# 3_PWR.net
KiCad netlist of a schematic drawn in Altium Designer
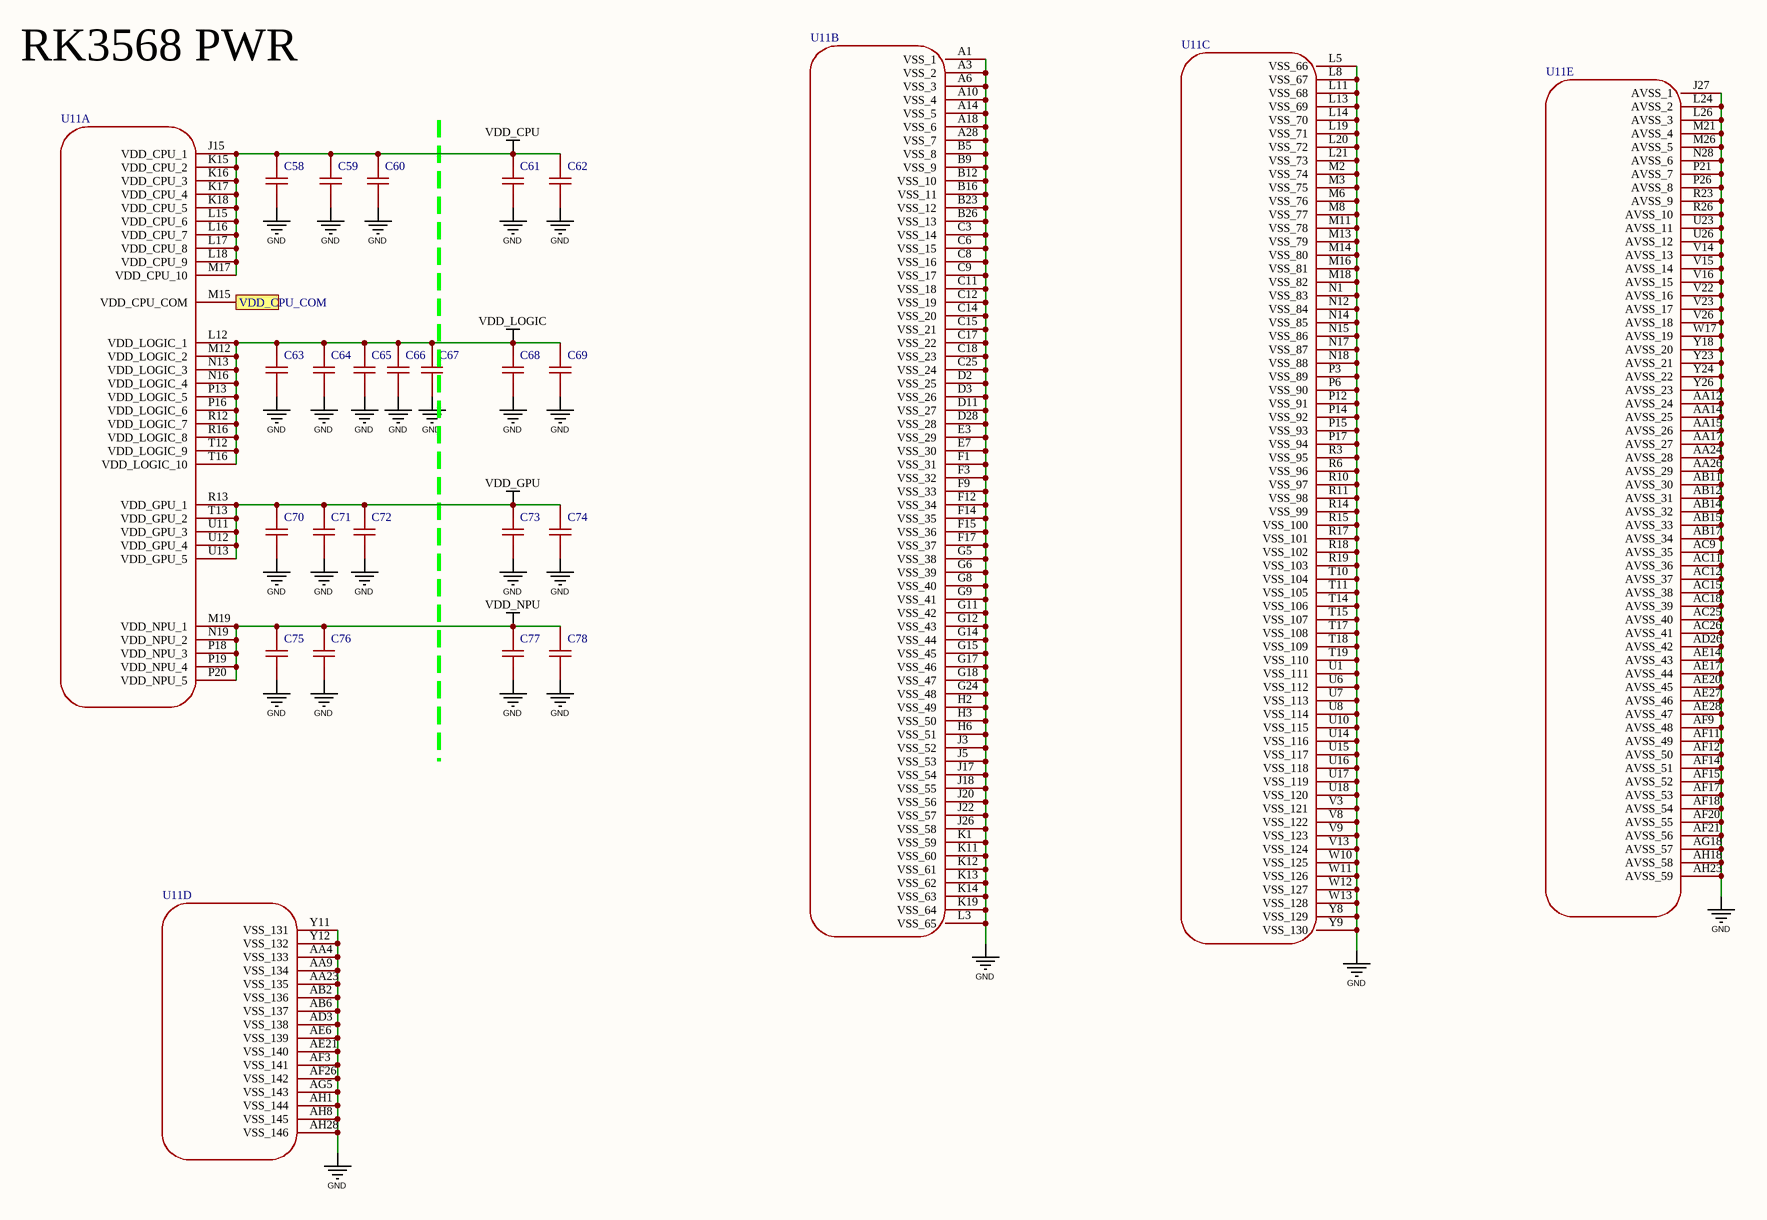
[diagram p0: 3_PWR.schdoc]

(export (version "E")
  (design (tool "Eeschema 10.0.6"))
  (components
    (comp (ref "C58")
      (value "100nF")
      (footprint "C0201")
      (description "容值:100nF;精度:±10%;额定电压:16V;材质(温度系数):X5R;")
      (fields
        (field (name "MANUFACTURER") "SAMSUNG(三星)")
        (field (name "MANUFACTURER PART") "CL03A104KO3NNNC")
      )
      (libsource (lib "altium-import") (part "root_0_CL03A104KO3NNNC_"))
    )
    (comp (ref "C59")
      (value "1uF")
      (footprint "C0402")
      (description "容值:1uF;精度:±10%;额定电压:25V;材质(温度系数):X5R;")
      (fields
        (field (name "MANUFACTURER") "SAMSUNG(三星)")
        (field (name "MANUFACTURER PART") "CL05A105KA5NQNC")
      )
      (libsource (lib "altium-import") (part "root_1_CL05A105KA5NQNC_"))
    )
    (comp (ref "C60")
      (value "22uF")
      (footprint "C0603")
      (description "容值:22uF;精度:±20%;额定电压:10V;材质(温度系数):X5R;")
      (fields
        (field (name "MANUFACTURER") "SAMSUNG(三星)")
        (field (name "MANUFACTURER PART") "CL10A226MP8NUNE")
      )
      (libsource (lib "altium-import") (part "root_1_CL10A226MP8NUNE_"))
    )
    (comp (ref "C61")
      (value "22uF")
      (footprint "C0603")
      (description "容值:22uF;精度:±20%;额定电压:10V;材质(温度系数):X5R;")
      (fields
        (field (name "MANUFACTURER") "SAMSUNG(三星)")
        (field (name "MANUFACTURER PART") "CL10A226MP8NUNE")
      )
      (libsource (lib "altium-import") (part "root_1_CL10A226MP8NUNE_"))
    )
    (comp (ref "C62")
      (value "22uF")
      (footprint "C0603")
      (description "容值:22uF;精度:±20%;额定电压:10V;材质(温度系数):X5R;")
      (fields
        (field (name "MANUFACTURER") "SAMSUNG(三星)")
        (field (name "MANUFACTURER PART") "CL10A226MP8NUNE")
      )
      (libsource (lib "altium-import") (part "root_1_CL10A226MP8NUNE_"))
    )
    (comp (ref "C63")
      (value "100nF")
      (footprint "C0201")
      (description "容值:100nF;精度:±10%;额定电压:16V;材质(温度系数):X5R;")
      (fields
        (field (name "MANUFACTURER") "SAMSUNG(三星)")
        (field (name "MANUFACTURER PART") "CL03A104KO3NNNC")
      )
      (libsource (lib "altium-import") (part "root_0_CL03A104KO3NNNC_"))
    )
    (comp (ref "C64")
      (value "4.7uF")
      (footprint "C0201")
      (description "容值:4.7uF;精度:±20%;额定电压:6.3V;材质(温度系数):X5R;")
      (fields
        (field (name "MANUFACTURER") "muRata(村田)")
        (field (name "MANUFACTURER PART") "GRM035R60J475ME15D")
      )
      (libsource (lib "altium-import") (part "root_0_GRM035R60J475ME15D_"))
    )
    (comp (ref "C65")
      (value "1uF")
      (footprint "C0402")
      (description "容值:1uF;精度:±10%;额定电压:25V;材质(温度系数):X5R;")
      (fields
        (field (name "MANUFACTURER") "SAMSUNG(三星)")
        (field (name "MANUFACTURER PART") "CL05A105KA5NQNC")
      )
      (libsource (lib "altium-import") (part "root_1_CL05A105KA5NQNC_"))
    )
    (comp (ref "C66")
      (value "1uF")
      (footprint "C0402")
      (description "容值:1uF;精度:±10%;额定电压:25V;材质(温度系数):X5R;")
      (fields
        (field (name "MANUFACTURER") "SAMSUNG(三星)")
        (field (name "MANUFACTURER PART") "CL05A105KA5NQNC")
      )
      (libsource (lib "altium-import") (part "root_1_CL05A105KA5NQNC_"))
    )
    (comp (ref "C67")
      (value "22uF")
      (footprint "C0603")
      (description "容值:22uF;精度:±20%;额定电压:10V;材质(温度系数):X5R;")
      (fields
        (field (name "MANUFACTURER") "SAMSUNG(三星)")
        (field (name "MANUFACTURER PART") "CL10A226MP8NUNE")
      )
      (libsource (lib "altium-import") (part "root_1_CL10A226MP8NUNE_"))
    )
    (comp (ref "C68")
      (value "22uF")
      (footprint "C0603")
      (description "容值:22uF;精度:±20%;额定电压:10V;材质(温度系数):X5R;")
      (fields
        (field (name "MANUFACTURER") "SAMSUNG(三星)")
        (field (name "MANUFACTURER PART") "CL10A226MP8NUNE")
      )
      (libsource (lib "altium-import") (part "root_1_CL10A226MP8NUNE_"))
    )
    (comp (ref "C69")
      (value "10uF")
      (footprint "C0402")
      (description "容值:10uF;精度:±20%;额定电压:10V;材质(温度系数):X5R;")
      (fields
        (field (name "MANUFACTURER") "SAMSUNG(三星)")
        (field (name "MANUFACTURER PART") "CL05A106MP5NUNC")
      )
      (libsource (lib "altium-import") (part "root_1_CL05A106MP5NUNC_"))
    )
    (comp (ref "C70")
      (value "100nF")
      (footprint "C0201")
      (description "容值:100nF;精度:±10%;额定电压:16V;材质(温度系数):X5R;")
      (fields
        (field (name "MANUFACTURER") "SAMSUNG(三星)")
        (field (name "MANUFACTURER PART") "CL03A104KO3NNNC")
      )
      (libsource (lib "altium-import") (part "root_0_CL03A104KO3NNNC_"))
    )
    (comp (ref "C71")
      (value "4.7uF")
      (footprint "C0201")
      (description "容值:4.7uF;精度:±20%;额定电压:6.3V;材质(温度系数):X5R;")
      (fields
        (field (name "MANUFACTURER") "muRata(村田)")
        (field (name "MANUFACTURER PART") "GRM035R60J475ME15D")
      )
      (libsource (lib "altium-import") (part "root_0_GRM035R60J475ME15D_"))
    )
    (comp (ref "C72")
      (value "22uF")
      (footprint "C0603")
      (description "容值:22uF;精度:±20%;额定电压:10V;材质(温度系数):X5R;")
      (fields
        (field (name "MANUFACTURER") "SAMSUNG(三星)")
        (field (name "MANUFACTURER PART") "CL10A226MP8NUNE")
      )
      (libsource (lib "altium-import") (part "root_1_CL10A226MP8NUNE_"))
    )
    (comp (ref "C73")
      (value "22uF")
      (footprint "C0603")
      (description "容值:22uF;精度:±20%;额定电压:10V;材质(温度系数):X5R;")
      (fields
        (field (name "MANUFACTURER") "SAMSUNG(三星)")
        (field (name "MANUFACTURER PART") "CL10A226MP8NUNE")
      )
      (libsource (lib "altium-import") (part "root_1_CL10A226MP8NUNE_"))
    )
    (comp (ref "C74")
      (value "10uF")
      (footprint "C0402")
      (description "容值:10uF;精度:±20%;额定电压:10V;材质(温度系数):X5R;")
      (fields
        (field (name "MANUFACTURER") "SAMSUNG(三星)")
        (field (name "MANUFACTURER PART") "CL05A106MP5NUNC")
      )
      (libsource (lib "altium-import") (part "root_1_CL05A106MP5NUNC_"))
    )
    (comp (ref "C75")
      (value "100nF")
      (footprint "C0201")
      (description "容值:100nF;精度:±10%;额定电压:16V;材质(温度系数):X5R;")
      (fields
        (field (name "MANUFACTURER") "SAMSUNG(三星)")
        (field (name "MANUFACTURER PART") "CL03A104KO3NNNC")
      )
      (libsource (lib "altium-import") (part "root_0_CL03A104KO3NNNC_"))
    )
    (comp (ref "C76")
      (value "22uF")
      (footprint "C0603")
      (description "容值:22uF;精度:±20%;额定电压:10V;材质(温度系数):X5R;")
      (fields
        (field (name "MANUFACTURER") "SAMSUNG(三星)")
        (field (name "MANUFACTURER PART") "CL10A226MP8NUNE")
      )
      (libsource (lib "altium-import") (part "root_1_CL10A226MP8NUNE_"))
    )
    (comp (ref "C77")
      (value "22uF")
      (footprint "C0603")
      (description "容值:22uF;精度:±20%;额定电压:10V;材质(温度系数):X5R;")
      (fields
        (field (name "MANUFACTURER") "SAMSUNG(三星)")
        (field (name "MANUFACTURER PART") "CL10A226MP8NUNE")
      )
      (libsource (lib "altium-import") (part "root_1_CL10A226MP8NUNE_"))
    )
    (comp (ref "C78")
      (value "10uF")
      (footprint "C0402")
      (description "容值:10uF;精度:±20%;额定电压:10V;材质(温度系数):X5R;")
      (fields
        (field (name "MANUFACTURER") "SAMSUNG(三星)")
        (field (name "MANUFACTURER PART") "CL05A106MP5NUNC")
      )
      (libsource (lib "altium-import") (part "root_1_CL05A106MP5NUNC_"))
    )
    (comp (ref "U11")
      (value "SOC_RK3568")
      (footprint "RK3568")
      (fields (field (name "MANUFACTURER") "Rockchip (瑞芯微)") (field (name "CREATED BY") "JJJ"))
      (libsource (lib "altium-import") (part "root_0_SOC_RK3568_"))
    )
  )
  (nets
    (net (code "1") (name "/VDD_CPU_COM") (class "Default")
      (node (ref "U11") (pin "M15") (pinfunction "VDD_CPU_COM_M15") (pintype "passive"))
    )
    (net (code "2") (name "GND") (class "Default")
      (node (ref "C58") (pin "1") (pinfunction "1_1") (pintype "passive"))
      (node (ref "C59") (pin "1") (pinfunction "1_1") (pintype "passive"))
      (node (ref "C60") (pin "1") (pinfunction "1_1") (pintype "passive"))
      (node (ref "C61") (pin "1") (pinfunction "1_1") (pintype "passive"))
      (node (ref "C62") (pin "1") (pinfunction "1_1") (pintype "passive"))
      (node (ref "C63") (pin "1") (pinfunction "1_1") (pintype "passive"))
      (node (ref "C64") (pin "1") (pinfunction "1_1") (pintype "passive"))
      (node (ref "C65") (pin "1") (pinfunction "1_1") (pintype "passive"))
      (node (ref "C66") (pin "1") (pinfunction "1_1") (pintype "passive"))
      (node (ref "C67") (pin "1") (pinfunction "1_1") (pintype "passive"))
      (node (ref "C68") (pin "1") (pinfunction "1_1") (pintype "passive"))
      (node (ref "C69") (pin "1") (pinfunction "1_1") (pintype "passive"))
      (node (ref "C70") (pin "1") (pinfunction "1_1") (pintype "passive"))
      (node (ref "C71") (pin "1") (pinfunction "1_1") (pintype "passive"))
      (node (ref "C72") (pin "1") (pinfunction "1_1") (pintype "passive"))
      (node (ref "C73") (pin "1") (pinfunction "1_1") (pintype "passive"))
      (node (ref "C74") (pin "1") (pinfunction "1_1") (pintype "passive"))
      (node (ref "C75") (pin "1") (pinfunction "1_1") (pintype "passive"))
      (node (ref "C76") (pin "1") (pinfunction "1_1") (pintype "passive"))
      (node (ref "C77") (pin "1") (pinfunction "1_1") (pintype "passive"))
      (node (ref "C78") (pin "1") (pinfunction "1_1") (pintype "passive"))
      (node (ref "U11") (pin "A1") (pinfunction "VSS_1_A1") (pintype "passive"))
      (node (ref "U11") (pin "A10") (pinfunction "VSS_4_A10") (pintype "passive"))
      (node (ref "U11") (pin "A14") (pinfunction "VSS_5_A14") (pintype "passive"))
      (node (ref "U11") (pin "A18") (pinfunction "VSS_6_A18") (pintype "passive"))
      (node (ref "U11") (pin "A28") (pinfunction "VSS_7_A28") (pintype "passive"))
      (node (ref "U11") (pin "A3") (pinfunction "VSS_2_A3") (pintype "passive"))
      (node (ref "U11") (pin "A6") (pinfunction "VSS_3_A6") (pintype "passive"))
      (node (ref "U11") (pin "AA12") (pinfunction "AVSS_24_AA12") (pintype "passive"))
      (node (ref "U11") (pin "AA14") (pinfunction "AVSS_25_AA14") (pintype "passive"))
      (node (ref "U11") (pin "AA15") (pinfunction "AVSS_26_AA15") (pintype "passive"))
      (node (ref "U11") (pin "AA17") (pinfunction "AVSS_27_AA17") (pintype "passive"))
      (node (ref "U11") (pin "AA23") (pinfunction "VSS_135_AA23") (pintype "passive"))
      (node (ref "U11") (pin "AA24") (pinfunction "AVSS_28_AA24") (pintype "passive"))
      (node (ref "U11") (pin "AA26") (pinfunction "AVSS_29_AA26") (pintype "passive"))
      (node (ref "U11") (pin "AA4") (pinfunction "VSS_133_AA4") (pintype "passive"))
      (node (ref "U11") (pin "AA9") (pinfunction "VSS_134_AA9") (pintype "passive"))
      (node (ref "U11") (pin "AB11") (pinfunction "AVSS_30_AB11") (pintype "passive"))
      (node (ref "U11") (pin "AB12") (pinfunction "AVSS_31_AB12") (pintype "passive"))
      (node (ref "U11") (pin "AB14") (pinfunction "AVSS_32_AB14") (pintype "passive"))
      (node (ref "U11") (pin "AB15") (pinfunction "AVSS_33_AB15") (pintype "passive"))
      (node (ref "U11") (pin "AB17") (pinfunction "AVSS_34_AB17") (pintype "passive"))
      (node (ref "U11") (pin "AB2") (pinfunction "VSS_136_AB2") (pintype "passive"))
      (node (ref "U11") (pin "AB6") (pinfunction "VSS_137_AB6") (pintype "passive"))
      (node (ref "U11") (pin "AC11") (pinfunction "AVSS_36_AC11") (pintype "passive"))
      (node (ref "U11") (pin "AC12") (pinfunction "AVSS_37_AC12") (pintype "passive"))
      (node (ref "U11") (pin "AC15") (pinfunction "AVSS_38_AC15") (pintype "passive"))
      (node (ref "U11") (pin "AC18") (pinfunction "AVSS_39_AC18") (pintype "passive"))
      (node (ref "U11") (pin "AC25") (pinfunction "AVSS_40_AC25") (pintype "passive"))
      (node (ref "U11") (pin "AC26") (pinfunction "AVSS_41_AC26") (pintype "passive"))
      (node (ref "U11") (pin "AC9") (pinfunction "AVSS_35_AC9") (pintype "passive"))
      (node (ref "U11") (pin "AD26") (pinfunction "AVSS_42_AD26") (pintype "passive"))
      (node (ref "U11") (pin "AD3") (pinfunction "VSS_138_AD3") (pintype "passive"))
      (node (ref "U11") (pin "AE14") (pinfunction "AVSS_43_AE14") (pintype "passive"))
      (node (ref "U11") (pin "AE17") (pinfunction "AVSS_44_AE17") (pintype "passive"))
      (node (ref "U11") (pin "AE20") (pinfunction "AVSS_45_AE20") (pintype "passive"))
      (node (ref "U11") (pin "AE21") (pinfunction "VSS_140_AE21") (pintype "passive"))
      (node (ref "U11") (pin "AE27") (pinfunction "AVSS_46_AE27") (pintype "passive"))
      (node (ref "U11") (pin "AE28") (pinfunction "AVSS_47_AE28") (pintype "passive"))
      (node (ref "U11") (pin "AE6") (pinfunction "VSS_139_AE6") (pintype "passive"))
      (node (ref "U11") (pin "AF11") (pinfunction "AVSS_49_AF11") (pintype "passive"))
      (node (ref "U11") (pin "AF12") (pinfunction "AVSS_50_AF12") (pintype "passive"))
      (node (ref "U11") (pin "AF14") (pinfunction "AVSS_51_AF14") (pintype "passive"))
      (node (ref "U11") (pin "AF15") (pinfunction "AVSS_52_AF15") (pintype "passive"))
      (node (ref "U11") (pin "AF17") (pinfunction "AVSS_53_AF17") (pintype "passive"))
      (node (ref "U11") (pin "AF18") (pinfunction "AVSS_54_AF18") (pintype "passive"))
      (node (ref "U11") (pin "AF20") (pinfunction "AVSS_55_AF20") (pintype "passive"))
      (node (ref "U11") (pin "AF21") (pinfunction "AVSS_56_AF21") (pintype "passive"))
      (node (ref "U11") (pin "AF26") (pinfunction "VSS_142_AF26") (pintype "passive"))
      (node (ref "U11") (pin "AF3") (pinfunction "VSS_141_AF3") (pintype "passive"))
      (node (ref "U11") (pin "AF9") (pinfunction "AVSS_48_AF9") (pintype "passive"))
      (node (ref "U11") (pin "AG18") (pinfunction "AVSS_57_AG18") (pintype "passive"))
      (node (ref "U11") (pin "AG5") (pinfunction "VSS_143_AG5") (pintype "passive"))
      (node (ref "U11") (pin "AH1") (pinfunction "VSS_144_AH1") (pintype "passive"))
      (node (ref "U11") (pin "AH18") (pinfunction "AVSS_58_AH18") (pintype "passive"))
      (node (ref "U11") (pin "AH23") (pinfunction "AVSS_59_AH23") (pintype "passive"))
      (node (ref "U11") (pin "AH28") (pinfunction "VSS_146_AH28") (pintype "passive"))
      (node (ref "U11") (pin "AH8") (pinfunction "VSS_145_AH8") (pintype "passive"))
      (node (ref "U11") (pin "B12") (pinfunction "VSS_10_B12") (pintype "passive"))
      (node (ref "U11") (pin "B16") (pinfunction "VSS_11_B16") (pintype "passive"))
      (node (ref "U11") (pin "B23") (pinfunction "VSS_12_B23") (pintype "passive"))
      (node (ref "U11") (pin "B26") (pinfunction "VSS_13_B26") (pintype "passive"))
      (node (ref "U11") (pin "B5") (pinfunction "VSS_8_B5") (pintype "passive"))
      (node (ref "U11") (pin "B9") (pinfunction "VSS_9_B9") (pintype "passive"))
      (node (ref "U11") (pin "C11") (pinfunction "VSS_18_C11") (pintype "passive"))
      (node (ref "U11") (pin "C12") (pinfunction "VSS_19_C12") (pintype "passive"))
      (node (ref "U11") (pin "C14") (pinfunction "VSS_20_C14") (pintype "passive"))
      (node (ref "U11") (pin "C15") (pinfunction "VSS_21_C15") (pintype "passive"))
      (node (ref "U11") (pin "C17") (pinfunction "VSS_22_C17") (pintype "passive"))
      (node (ref "U11") (pin "C18") (pinfunction "VSS_23_C18") (pintype "passive"))
      (node (ref "U11") (pin "C25") (pinfunction "VSS_24_C25") (pintype "passive"))
      (node (ref "U11") (pin "C3") (pinfunction "VSS_14_C3") (pintype "passive"))
      (node (ref "U11") (pin "C6") (pinfunction "VSS_15_C6") (pintype "passive"))
      (node (ref "U11") (pin "C8") (pinfunction "VSS_16_C8") (pintype "passive"))
      (node (ref "U11") (pin "C9") (pinfunction "VSS_17_C9") (pintype "passive"))
      (node (ref "U11") (pin "D11") (pinfunction "VSS_27_D11") (pintype "passive"))
      (node (ref "U11") (pin "D2") (pinfunction "VSS_25_D2") (pintype "passive"))
      (node (ref "U11") (pin "D28") (pinfunction "VSS_28_D28") (pintype "passive"))
      (node (ref "U11") (pin "D3") (pinfunction "VSS_26_D3") (pintype "passive"))
      (node (ref "U11") (pin "E3") (pinfunction "VSS_29_E3") (pintype "passive"))
      (node (ref "U11") (pin "E7") (pinfunction "VSS_30_E7") (pintype "passive"))
      (node (ref "U11") (pin "F1") (pinfunction "VSS_31_F1") (pintype "passive"))
      (node (ref "U11") (pin "F12") (pinfunction "VSS_34_F12") (pintype "passive"))
      (node (ref "U11") (pin "F14") (pinfunction "VSS_35_F14") (pintype "passive"))
      (node (ref "U11") (pin "F15") (pinfunction "VSS_36_F15") (pintype "passive"))
      (node (ref "U11") (pin "F17") (pinfunction "VSS_37_F17") (pintype "passive"))
      (node (ref "U11") (pin "F3") (pinfunction "VSS_32_F3") (pintype "passive"))
      (node (ref "U11") (pin "F9") (pinfunction "VSS_33_F9") (pintype "passive"))
      (node (ref "U11") (pin "G11") (pinfunction "VSS_42_G11") (pintype "passive"))
      (node (ref "U11") (pin "G12") (pinfunction "VSS_43_G12") (pintype "passive"))
      (node (ref "U11") (pin "G14") (pinfunction "VSS_44_G14") (pintype "passive"))
      (node (ref "U11") (pin "G15") (pinfunction "VSS_45_G15") (pintype "passive"))
      (node (ref "U11") (pin "G17") (pinfunction "VSS_46_G17") (pintype "passive"))
      (node (ref "U11") (pin "G18") (pinfunction "VSS_47_G18") (pintype "passive"))
      (node (ref "U11") (pin "G24") (pinfunction "VSS_48_G24") (pintype "passive"))
      (node (ref "U11") (pin "G5") (pinfunction "VSS_38_G5") (pintype "passive"))
      (node (ref "U11") (pin "G6") (pinfunction "VSS_39_G6") (pintype "passive"))
      (node (ref "U11") (pin "G8") (pinfunction "VSS_40_G8") (pintype "passive"))
      (node (ref "U11") (pin "G9") (pinfunction "VSS_41_G9") (pintype "passive"))
      (node (ref "U11") (pin "H2") (pinfunction "VSS_49_H2") (pintype "passive"))
      (node (ref "U11") (pin "H3") (pinfunction "VSS_50_H3") (pintype "passive"))
      (node (ref "U11") (pin "H6") (pinfunction "VSS_51_H6") (pintype "passive"))
      (node (ref "U11") (pin "J17") (pinfunction "VSS_54_J17") (pintype "passive"))
      (node (ref "U11") (pin "J18") (pinfunction "VSS_55_J18") (pintype "passive"))
      (node (ref "U11") (pin "J20") (pinfunction "VSS_56_J20") (pintype "passive"))
      (node (ref "U11") (pin "J22") (pinfunction "VSS_57_J22") (pintype "passive"))
      (node (ref "U11") (pin "J26") (pinfunction "VSS_58_J26") (pintype "passive"))
      (node (ref "U11") (pin "J27") (pinfunction "AVSS_1_J27") (pintype "passive"))
      (node (ref "U11") (pin "J3") (pinfunction "VSS_52_J3") (pintype "passive"))
      (node (ref "U11") (pin "J5") (pinfunction "VSS_53_J5") (pintype "passive"))
      (node (ref "U11") (pin "K1") (pinfunction "VSS_59_K1") (pintype "passive"))
      (node (ref "U11") (pin "K11") (pinfunction "VSS_60_K11") (pintype "passive"))
      (node (ref "U11") (pin "K12") (pinfunction "VSS_61_K12") (pintype "passive"))
      (node (ref "U11") (pin "K13") (pinfunction "VSS_62_K13") (pintype "passive"))
      (node (ref "U11") (pin "K14") (pinfunction "VSS_63_K14") (pintype "passive"))
      (node (ref "U11") (pin "K19") (pinfunction "VSS_64_K19") (pintype "passive"))
      (node (ref "U11") (pin "L11") (pinfunction "VSS_68_L11") (pintype "passive"))
      (node (ref "U11") (pin "L13") (pinfunction "VSS_69_L13") (pintype "passive"))
      (node (ref "U11") (pin "L14") (pinfunction "VSS_70_L14") (pintype "passive"))
      (node (ref "U11") (pin "L19") (pinfunction "VSS_71_L19") (pintype "passive"))
      (node (ref "U11") (pin "L20") (pinfunction "VSS_72_L20") (pintype "passive"))
      (node (ref "U11") (pin "L21") (pinfunction "VSS_73_L21") (pintype "passive"))
      (node (ref "U11") (pin "L24") (pinfunction "AVSS_2_L24") (pintype "passive"))
      (node (ref "U11") (pin "L26") (pinfunction "AVSS_3_L26") (pintype "passive"))
      (node (ref "U11") (pin "L3") (pinfunction "VSS_65_L3") (pintype "passive"))
      (node (ref "U11") (pin "L5") (pinfunction "VSS_66_L5") (pintype "passive"))
      (node (ref "U11") (pin "L8") (pinfunction "VSS_67_L8") (pintype "passive"))
      (node (ref "U11") (pin "M11") (pinfunction "VSS_78_M11") (pintype "passive"))
      (node (ref "U11") (pin "M13") (pinfunction "VSS_79_M13") (pintype "passive"))
      (node (ref "U11") (pin "M14") (pinfunction "VSS_80_M14") (pintype "passive"))
      (node (ref "U11") (pin "M16") (pinfunction "VSS_81_M16") (pintype "passive"))
      (node (ref "U11") (pin "M18") (pinfunction "VSS_82_M18") (pintype "passive"))
      (node (ref "U11") (pin "M2") (pinfunction "VSS_74_M2") (pintype "passive"))
      (node (ref "U11") (pin "M21") (pinfunction "AVSS_4_M21") (pintype "passive"))
      (node (ref "U11") (pin "M26") (pinfunction "AVSS_5_M26") (pintype "passive"))
      (node (ref "U11") (pin "M3") (pinfunction "VSS_75_M3") (pintype "passive"))
      (node (ref "U11") (pin "M6") (pinfunction "VSS_76_M6") (pintype "passive"))
      (node (ref "U11") (pin "M8") (pinfunction "VSS_77_M8") (pintype "passive"))
      (node (ref "U11") (pin "N1") (pinfunction "VSS_83_N1") (pintype "passive"))
      (node (ref "U11") (pin "N12") (pinfunction "VSS_84_N12") (pintype "passive"))
      (node (ref "U11") (pin "N14") (pinfunction "VSS_85_N14") (pintype "passive"))
      (node (ref "U11") (pin "N15") (pinfunction "VSS_86_N15") (pintype "passive"))
      (node (ref "U11") (pin "N17") (pinfunction "VSS_87_N17") (pintype "passive"))
      (node (ref "U11") (pin "N18") (pinfunction "VSS_88_N18") (pintype "passive"))
      (node (ref "U11") (pin "N28") (pinfunction "AVSS_6_N28") (pintype "passive"))
      (node (ref "U11") (pin "P12") (pinfunction "VSS_91_P12") (pintype "passive"))
      (node (ref "U11") (pin "P14") (pinfunction "VSS_92_P14") (pintype "passive"))
      (node (ref "U11") (pin "P15") (pinfunction "VSS_93_P15") (pintype "passive"))
      (node (ref "U11") (pin "P17") (pinfunction "VSS_94_P17") (pintype "passive"))
      (node (ref "U11") (pin "P21") (pinfunction "AVSS_7_P21") (pintype "passive"))
      (node (ref "U11") (pin "P26") (pinfunction "AVSS_8_P26") (pintype "passive"))
      (node (ref "U11") (pin "P3") (pinfunction "VSS_89_P3") (pintype "passive"))
      (node (ref "U11") (pin "P6") (pinfunction "VSS_90_P6") (pintype "passive"))
      (node (ref "U11") (pin "R10") (pinfunction "VSS_97_R10") (pintype "passive"))
      (node (ref "U11") (pin "R11") (pinfunction "VSS_98_R11") (pintype "passive"))
      (node (ref "U11") (pin "R14") (pinfunction "VSS_99_R14") (pintype "passive"))
      (node (ref "U11") (pin "R15") (pinfunction "VSS_100_R15") (pintype "passive"))
      (node (ref "U11") (pin "R17") (pinfunction "VSS_101_R17") (pintype "passive"))
      (node (ref "U11") (pin "R18") (pinfunction "VSS_102_R18") (pintype "passive"))
      (node (ref "U11") (pin "R19") (pinfunction "VSS_103_R19") (pintype "passive"))
      (node (ref "U11") (pin "R23") (pinfunction "AVSS_9_R23") (pintype "passive"))
      (node (ref "U11") (pin "R26") (pinfunction "AVSS_10_R26") (pintype "passive"))
      (node (ref "U11") (pin "R3") (pinfunction "VSS_95_R3") (pintype "passive"))
      (node (ref "U11") (pin "R6") (pinfunction "VSS_96_R6") (pintype "passive"))
      (node (ref "U11") (pin "T10") (pinfunction "VSS_104_T10") (pintype "passive"))
      (node (ref "U11") (pin "T11") (pinfunction "VSS_105_T11") (pintype "passive"))
      (node (ref "U11") (pin "T14") (pinfunction "VSS_106_T14") (pintype "passive"))
      (node (ref "U11") (pin "T15") (pinfunction "VSS_107_T15") (pintype "passive"))
      (node (ref "U11") (pin "T17") (pinfunction "VSS_108_T17") (pintype "passive"))
      (node (ref "U11") (pin "T18") (pinfunction "VSS_109_T18") (pintype "passive"))
      (node (ref "U11") (pin "T19") (pinfunction "VSS_110_T19") (pintype "passive"))
      (node (ref "U11") (pin "U1") (pinfunction "VSS_111_U1") (pintype "passive"))
      (node (ref "U11") (pin "U10") (pinfunction "VSS_115_U10") (pintype "passive"))
      (node (ref "U11") (pin "U14") (pinfunction "VSS_116_U14") (pintype "passive"))
      (node (ref "U11") (pin "U15") (pinfunction "VSS_117_U15") (pintype "passive"))
      (node (ref "U11") (pin "U16") (pinfunction "VSS_118_U16") (pintype "passive"))
      (node (ref "U11") (pin "U17") (pinfunction "VSS_119_U17") (pintype "passive"))
      (node (ref "U11") (pin "U18") (pinfunction "VSS_120_U18") (pintype "passive"))
      (node (ref "U11") (pin "U23") (pinfunction "AVSS_11_U23") (pintype "passive"))
      (node (ref "U11") (pin "U26") (pinfunction "AVSS_12_U26") (pintype "passive"))
      (node (ref "U11") (pin "U6") (pinfunction "VSS_112_U6") (pintype "passive"))
      (node (ref "U11") (pin "U7") (pinfunction "VSS_113_U7") (pintype "passive"))
      (node (ref "U11") (pin "U8") (pinfunction "VSS_114_U8") (pintype "passive"))
      (node (ref "U11") (pin "V13") (pinfunction "VSS_124_V13") (pintype "passive"))
      (node (ref "U11") (pin "V14") (pinfunction "AVSS_13_V14") (pintype "passive"))
      (node (ref "U11") (pin "V15") (pinfunction "AVSS_14_V15") (pintype "passive"))
      (node (ref "U11") (pin "V16") (pinfunction "AVSS_15_V16") (pintype "passive"))
      (node (ref "U11") (pin "V22") (pinfunction "AVSS_16_V22") (pintype "passive"))
      (node (ref "U11") (pin "V23") (pinfunction "AVSS_17_V23") (pintype "passive"))
      (node (ref "U11") (pin "V26") (pinfunction "AVSS_18_V26") (pintype "passive"))
      (node (ref "U11") (pin "V3") (pinfunction "VSS_121_V3") (pintype "passive"))
      (node (ref "U11") (pin "V8") (pinfunction "VSS_122_V8") (pintype "passive"))
      (node (ref "U11") (pin "V9") (pinfunction "VSS_123_V9") (pintype "passive"))
      (node (ref "U11") (pin "W10") (pinfunction "VSS_125_W10") (pintype "passive"))
      (node (ref "U11") (pin "W11") (pinfunction "VSS_126_W11") (pintype "passive"))
      (node (ref "U11") (pin "W12") (pinfunction "VSS_127_W12") (pintype "passive"))
      (node (ref "U11") (pin "W13") (pinfunction "VSS_128_W13") (pintype "passive"))
      (node (ref "U11") (pin "W17") (pinfunction "AVSS_19_W17") (pintype "passive"))
      (node (ref "U11") (pin "Y11") (pinfunction "VSS_131_Y11") (pintype "passive"))
      (node (ref "U11") (pin "Y12") (pinfunction "VSS_132_Y12") (pintype "passive"))
      (node (ref "U11") (pin "Y18") (pinfunction "AVSS_20_Y18") (pintype "passive"))
      (node (ref "U11") (pin "Y23") (pinfunction "AVSS_21_Y23") (pintype "passive"))
      (node (ref "U11") (pin "Y24") (pinfunction "AVSS_22_Y24") (pintype "passive"))
      (node (ref "U11") (pin "Y26") (pinfunction "AVSS_23_Y26") (pintype "passive"))
      (node (ref "U11") (pin "Y8") (pinfunction "VSS_129_Y8") (pintype "passive"))
      (node (ref "U11") (pin "Y9") (pinfunction "VSS_130_Y9") (pintype "passive"))
    )
    (net (code "3") (name "VDD_CPU") (class "Default")
      (node (ref "C58") (pin "2") (pinfunction "2_2") (pintype "passive"))
      (node (ref "C59") (pin "2") (pinfunction "2_2") (pintype "passive"))
      (node (ref "C60") (pin "2") (pinfunction "2_2") (pintype "passive"))
      (node (ref "C61") (pin "2") (pinfunction "2_2") (pintype "passive"))
      (node (ref "C62") (pin "2") (pinfunction "2_2") (pintype "passive"))
      (node (ref "U11") (pin "J15") (pinfunction "VDD_CPU_1_J15") (pintype "passive"))
      (node (ref "U11") (pin "K15") (pinfunction "VDD_CPU_2_K15") (pintype "passive"))
      (node (ref "U11") (pin "K16") (pinfunction "VDD_CPU_3_K16") (pintype "passive"))
      (node (ref "U11") (pin "K17") (pinfunction "VDD_CPU_4_K17") (pintype "passive"))
      (node (ref "U11") (pin "K18") (pinfunction "VDD_CPU_5_K18") (pintype "passive"))
      (node (ref "U11") (pin "L15") (pinfunction "VDD_CPU_6_L15") (pintype "passive"))
      (node (ref "U11") (pin "L16") (pinfunction "VDD_CPU_7_L16") (pintype "passive"))
      (node (ref "U11") (pin "L17") (pinfunction "VDD_CPU_8_L17") (pintype "passive"))
      (node (ref "U11") (pin "L18") (pinfunction "VDD_CPU_9_L18") (pintype "passive"))
      (node (ref "U11") (pin "M17") (pinfunction "VDD_CPU_10_M17") (pintype "passive"))
    )
    (net (code "4") (name "VDD_GPU") (class "Default")
      (node (ref "C70") (pin "2") (pinfunction "2_2") (pintype "passive"))
      (node (ref "C71") (pin "2") (pinfunction "2_2") (pintype "passive"))
      (node (ref "C72") (pin "2") (pinfunction "2_2") (pintype "passive"))
      (node (ref "C73") (pin "2") (pinfunction "2_2") (pintype "passive"))
      (node (ref "C74") (pin "2") (pinfunction "2_2") (pintype "passive"))
      (node (ref "U11") (pin "R13") (pinfunction "VDD_GPU_1_R13") (pintype "passive"))
      (node (ref "U11") (pin "T13") (pinfunction "VDD_GPU_2_T13") (pintype "passive"))
      (node (ref "U11") (pin "U11") (pinfunction "VDD_GPU_3_U11") (pintype "passive"))
      (node (ref "U11") (pin "U12") (pinfunction "VDD_GPU_4_U12") (pintype "passive"))
      (node (ref "U11") (pin "U13") (pinfunction "VDD_GPU_5_U13") (pintype "passive"))
    )
    (net (code "5") (name "VDD_LOGIC") (class "Default")
      (node (ref "C63") (pin "2") (pinfunction "2_2") (pintype "passive"))
      (node (ref "C64") (pin "2") (pinfunction "2_2") (pintype "passive"))
      (node (ref "C65") (pin "2") (pinfunction "2_2") (pintype "passive"))
      (node (ref "C66") (pin "2") (pinfunction "2_2") (pintype "passive"))
      (node (ref "C67") (pin "2") (pinfunction "2_2") (pintype "passive"))
      (node (ref "C68") (pin "2") (pinfunction "2_2") (pintype "passive"))
      (node (ref "C69") (pin "2") (pinfunction "2_2") (pintype "passive"))
      (node (ref "U11") (pin "L12") (pinfunction "VDD_LOGIC_1_L12") (pintype "passive"))
      (node (ref "U11") (pin "M12") (pinfunction "VDD_LOGIC_2_M12") (pintype "passive"))
      (node (ref "U11") (pin "N13") (pinfunction "VDD_LOGIC_3_N13") (pintype "passive"))
      (node (ref "U11") (pin "N16") (pinfunction "VDD_LOGIC_4_N16") (pintype "passive"))
      (node (ref "U11") (pin "P13") (pinfunction "VDD_LOGIC_5_P13") (pintype "passive"))
      (node (ref "U11") (pin "P16") (pinfunction "VDD_LOGIC_6_P16") (pintype "passive"))
      (node (ref "U11") (pin "R12") (pinfunction "VDD_LOGIC_7_R12") (pintype "passive"))
      (node (ref "U11") (pin "R16") (pinfunction "VDD_LOGIC_8_R16") (pintype "passive"))
      (node (ref "U11") (pin "T12") (pinfunction "VDD_LOGIC_9_T12") (pintype "passive"))
      (node (ref "U11") (pin "T16") (pinfunction "VDD_LOGIC_10_T16") (pintype "passive"))
    )
    (net (code "6") (name "VDD_NPU") (class "Default")
      (node (ref "C75") (pin "2") (pinfunction "2_2") (pintype "passive"))
      (node (ref "C76") (pin "2") (pinfunction "2_2") (pintype "passive"))
      (node (ref "C77") (pin "2") (pinfunction "2_2") (pintype "passive"))
      (node (ref "C78") (pin "2") (pinfunction "2_2") (pintype "passive"))
      (node (ref "U11") (pin "M19") (pinfunction "VDD_NPU_1_M19") (pintype "passive"))
      (node (ref "U11") (pin "N19") (pinfunction "VDD_NPU_2_N19") (pintype "passive"))
      (node (ref "U11") (pin "P18") (pinfunction "VDD_NPU_3_P18") (pintype "passive"))
      (node (ref "U11") (pin "P19") (pinfunction "VDD_NPU_4_P19") (pintype "passive"))
      (node (ref "U11") (pin "P20") (pinfunction "VDD_NPU_5_P20") (pintype "passive"))
    )
  )
)
